# PowerSupply.net
KiCad netlist of a schematic drawn in EAGLE
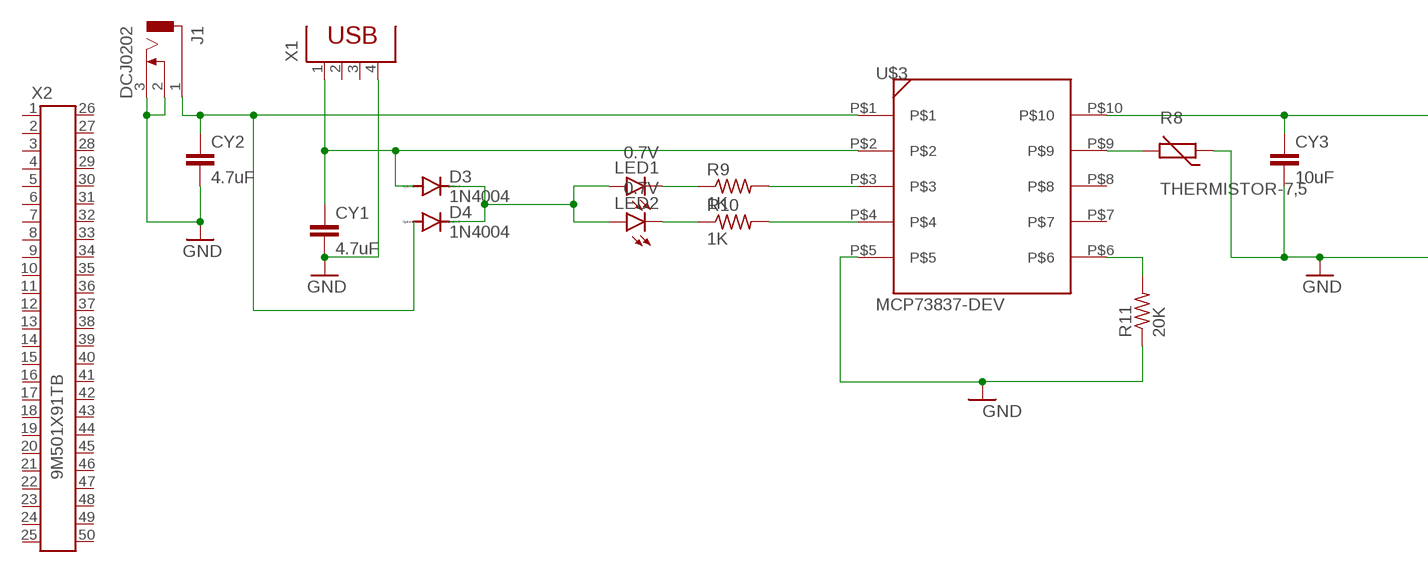
[diagram p0: schematic, sheet 1, part 1 of 2]
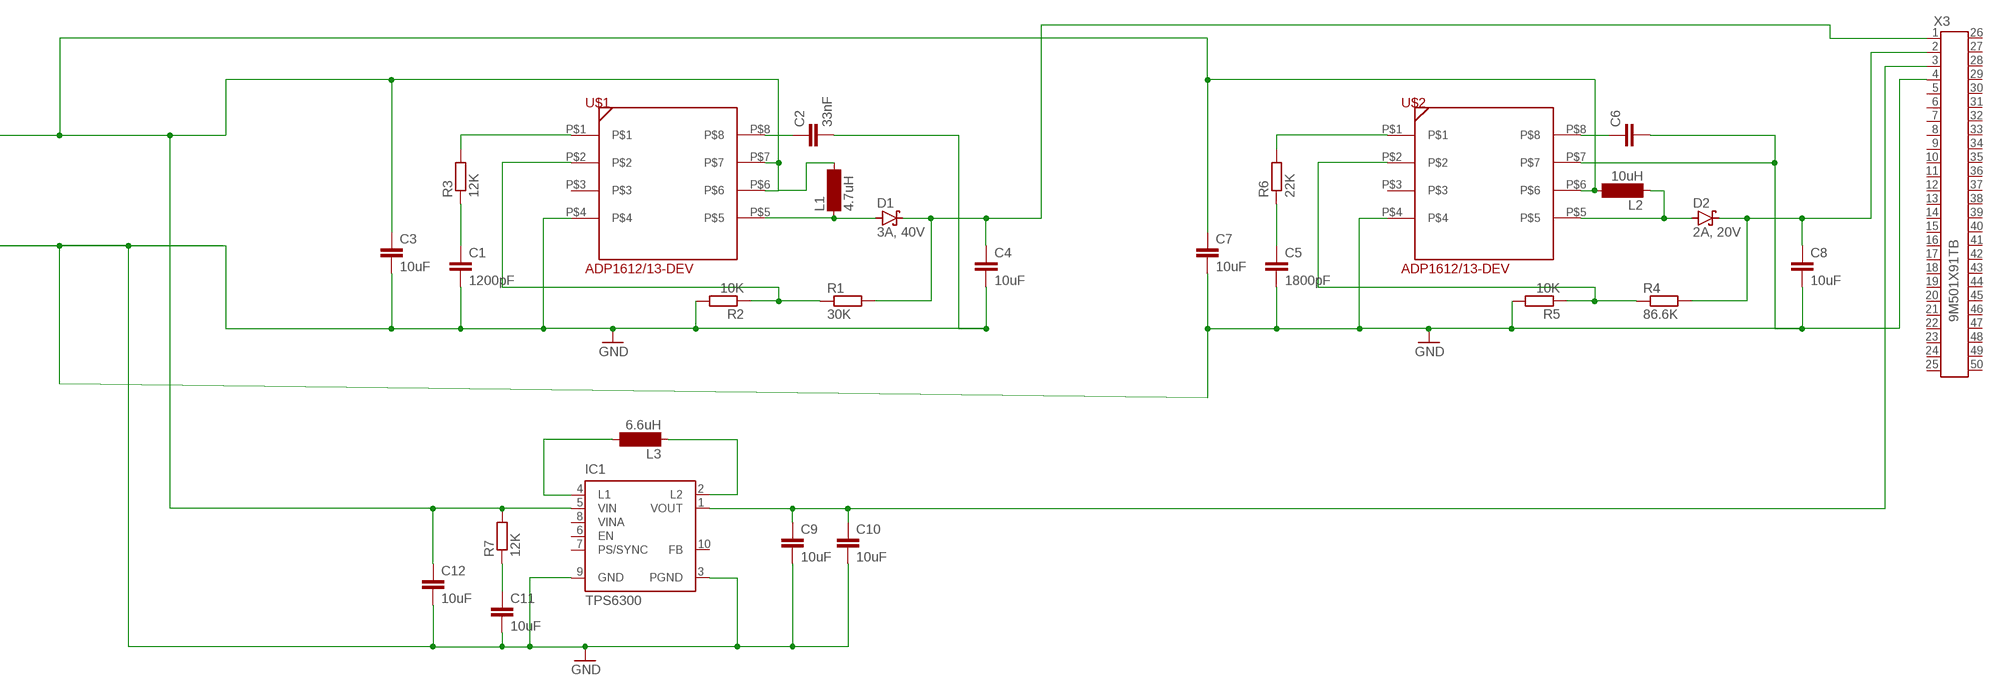
[diagram p1: schematic, sheet 1, part 2 of 2]

(export (version "E")
  (design (tool "Eeschema 10.0.6"))
  (components
    (comp (ref "C1")
      (value "1200pF")
      (footprint "eagle-import:C2.5-2")
      (libsource (lib "eagle-import") (part "C2.5/2"))
    )
    (comp (ref "C2")
      (value "33nF")
      (footprint "eagle-import:C2.5-2")
      (libsource (lib "eagle-import") (part "C2.5/2"))
    )
    (comp (ref "C3")
      (value "10uF")
      (footprint "eagle-import:C2.5-2")
      (libsource (lib "eagle-import") (part "C2.5/2"))
    )
    (comp (ref "C4")
      (value "10uF")
      (footprint "eagle-import:C2.5-2")
      (libsource (lib "eagle-import") (part "C2.5/2"))
    )
    (comp (ref "C5")
      (value "1800pF")
      (footprint "eagle-import:C2.5-2")
      (libsource (lib "eagle-import") (part "C2.5/2"))
    )
    (comp (ref "C6")
      (value "C2.5/2")
      (footprint "eagle-import:C2.5-2")
      (libsource (lib "eagle-import") (part "C2.5/2"))
    )
    (comp (ref "C7")
      (value "10uF")
      (footprint "eagle-import:C2.5-2")
      (libsource (lib "eagle-import") (part "C2.5/2"))
    )
    (comp (ref "C8")
      (value "10uF")
      (footprint "eagle-import:C2.5-2")
      (libsource (lib "eagle-import") (part "C2.5/2"))
    )
    (comp (ref "C9")
      (value "10uF")
      (footprint "eagle-import:C2.5-3")
      (libsource (lib "eagle-import") (part "C2,5-3"))
    )
    (comp (ref "C10")
      (value "10uF")
      (footprint "eagle-import:C2.5-3")
      (libsource (lib "eagle-import") (part "C2,5-3"))
    )
    (comp (ref "C11")
      (value "10uF")
      (footprint "eagle-import:C2.5-3")
      (libsource (lib "eagle-import") (part "C2,5-3"))
    )
    (comp (ref "C12")
      (value "10uF")
      (footprint "eagle-import:C2.5-3")
      (libsource (lib "eagle-import") (part "C2,5-3"))
    )
    (comp (ref "CY1")
      (value "4.7uF")
      (footprint "eagle-import:YC10B4")
      (libsource (lib "eagle-import") (part "CYYC10B4"))
    )
    (comp (ref "CY2")
      (value "4.7uF")
      (footprint "eagle-import:YC10B4")
      (libsource (lib "eagle-import") (part "CYYC10B4"))
    )
    (comp (ref "CY3")
      (value "10uF")
      (footprint "eagle-import:YC10B4")
      (libsource (lib "eagle-import") (part "CYYC10B4"))
    )
    (comp (ref "D1")
      (value "3A, 40V")
      (footprint "eagle-import:DO13M")
      (libsource (lib "eagle-import") (part "1N5638"))
    )
    (comp (ref "D2")
      (value "2A, 20V")
      (footprint "eagle-import:DO13M")
      (libsource (lib "eagle-import") (part "1N5638"))
    )
    (comp (ref "D3")
      (value "1N4004")
      (footprint "eagle-import:DO41-10")
      (libsource (lib "eagle-import") (part "1N4004"))
    )
    (comp (ref "D4")
      (value "1N4004")
      (footprint "eagle-import:DO41-10")
      (libsource (lib "eagle-import") (part "1N4004"))
    )
    (comp (ref "IC1")
      (value "TPS6300")
      (footprint "eagle-import:DRC-S-PVSON-N10")
      (fields (field (name "MPN") "TPS63000DRCTG4"))
      (libsource (lib "eagle-import") (part "TPS6300"))
    )
    (comp (ref "J1")
      (value "DCJ0202")
      (footprint "eagle-import:DCJ0202")
      (libsource (lib "eagle-import") (part "DCJ0202"))
    )
    (comp (ref "L1")
      (value "4.7uH")
      (footprint "eagle-import:SM-NE45")
      (libsource (lib "eagle-import") (part "SM-NE45"))
    )
    (comp (ref "L2")
      (value "10uH")
      (footprint "eagle-import:SM-NE45")
      (libsource (lib "eagle-import") (part "SM-NE45"))
    )
    (comp (ref "L3")
      (value "6.6uH")
      (footprint "eagle-import:SM-NE45")
      (libsource (lib "eagle-import") (part "SM-NE45"))
    )
    (comp (ref "LED1")
      (value "0.7V")
      (footprint "eagle-import:SMARTLED-TTW")
      (libsource (lib "eagle-import") (part "LED"))
    )
    (comp (ref "LED2")
      (value "0.7V")
      (footprint "eagle-import:SMARTLED-TTW")
      (libsource (lib "eagle-import") (part "LED"))
    )
    (comp (ref "R1")
      (value "30K")
      (footprint "eagle-import:0204V")
      (libsource (lib "eagle-import") (part "R-EU_0204/2V"))
    )
    (comp (ref "R2")
      (value "10K")
      (footprint "eagle-import:0204V")
      (libsource (lib "eagle-import") (part "R-EU_0204/2V"))
    )
    (comp (ref "R3")
      (value "12K")
      (footprint "eagle-import:0204V")
      (libsource (lib "eagle-import") (part "R-EU_0204/2V"))
    )
    (comp (ref "R4")
      (value "86.6K")
      (footprint "eagle-import:0204V")
      (libsource (lib "eagle-import") (part "R-EU_0204/2V"))
    )
    (comp (ref "R5")
      (value "10K")
      (footprint "eagle-import:0204V")
      (libsource (lib "eagle-import") (part "R-EU_0204/2V"))
    )
    (comp (ref "R6")
      (value "22K")
      (footprint "eagle-import:0204V")
      (libsource (lib "eagle-import") (part "R-EU_0204/2V"))
    )
    (comp (ref "R7")
      (value "12K")
      (footprint "eagle-import:0204V")
      (libsource (lib "eagle-import") (part "R-EU_0204/2V"))
    )
    (comp (ref "R8")
      (value "THERMISTOR-7,5")
      (footprint "eagle-import:R-7,5")
      (libsource (lib "eagle-import") (part "THERMISTOR-7,5"))
    )
    (comp (ref "R9")
      (value "1K")
      (footprint "eagle-import:0204V")
      (libsource (lib "eagle-import") (part "R-US_0204/2V"))
    )
    (comp (ref "R10")
      (value "1K")
      (footprint "eagle-import:0204V")
      (libsource (lib "eagle-import") (part "R-US_0204/2V"))
    )
    (comp (ref "R11")
      (value "20K")
      (footprint "eagle-import:0204V")
      (libsource (lib "eagle-import") (part "R-US_0204/2V"))
    )
    (comp (ref "U$1")
      (value "ADP1612/13-DEV")
      (footprint "eagle-import:ADP1612_13")
      (libsource (lib "eagle-import") (part "ADP1612/13-DEV"))
    )
    (comp (ref "U$2")
      (value "ADP1612/13-DEV")
      (footprint "eagle-import:ADP1612_13")
      (libsource (lib "eagle-import") (part "ADP1612/13-DEV"))
    )
    (comp (ref "U$3")
      (value "MCP73837-DEV")
      (footprint "eagle-import:MCP73837-FCI")
      (libsource (lib "eagle-import") (part "MCP73837-DEV"))
    )
    (comp (ref "X1")
      (value "PN61729")
      (footprint "eagle-import:PN61729")
      (libsource (lib "eagle-import") (part "PN61729"))
    )
    (comp (ref "X2")
      (value "9M501X91TB")
      (footprint "eagle-import:9M501X91")
      (libsource (lib "eagle-import") (part "9M501X91TB"))
    )
    (comp (ref "X3")
      (value "9M501X91TB")
      (footprint "eagle-import:9M501X91")
      (libsource (lib "eagle-import") (part "9M501X91TB"))
    )
  )
  (nets
    (net (code "1") (name "GND") (class "Default")
      (node (ref "C1") (pin "2") (pinfunction "2_2") (pintype "passive"))
      (node (ref "C10") (pin "2") (pinfunction "2_2") (pintype "passive"))
      (node (ref "C11") (pin "2") (pinfunction "2_2") (pintype "passive"))
      (node (ref "C12") (pin "2") (pinfunction "2_2") (pintype "passive"))
      (node (ref "C2") (pin "2") (pinfunction "2_2") (pintype "passive"))
      (node (ref "C3") (pin "2") (pinfunction "2_2") (pintype "passive"))
      (node (ref "C4") (pin "2") (pinfunction "2_2") (pintype "passive"))
      (node (ref "C5") (pin "2") (pinfunction "2_2") (pintype "passive"))
      (node (ref "C6") (pin "2") (pinfunction "2_2") (pintype "passive"))
      (node (ref "C7") (pin "2") (pinfunction "2_2") (pintype "passive"))
      (node (ref "C8") (pin "2") (pinfunction "2_2") (pintype "passive"))
      (node (ref "C9") (pin "2") (pinfunction "2_2") (pintype "passive"))
      (node (ref "CY1") (pin "2") (pinfunction "2_2") (pintype "passive"))
      (node (ref "CY2") (pin "2") (pinfunction "2_2") (pintype "passive"))
      (node (ref "CY3") (pin "2") (pinfunction "2_2") (pintype "passive"))
      (node (ref "IC1") (pin "3") (pinfunction "PGND_3") (pintype "power_in"))
      (node (ref "IC1") (pin "9") (pinfunction "GND_9") (pintype "power_in"))
      (node (ref "J1") (pin "2") (pinfunction "2_2") (pintype "passive"))
      (node (ref "J1") (pin "3") (pinfunction "3_3") (pintype "passive"))
      (node (ref "R11") (pin "1") (pinfunction "1_1") (pintype "passive"))
      (node (ref "R2") (pin "2") (pinfunction "2_2") (pintype "passive"))
      (node (ref "R5") (pin "2") (pinfunction "2_2") (pintype "passive"))
      (node (ref "R8") (pin "1") (pinfunction "1_1") (pintype "passive"))
      (node (ref "U$1") (pin "P$4") (pinfunction "P$4_P$4") (pintype "bidirectional"))
      (node (ref "U$2") (pin "P$4") (pinfunction "P$4_P$4") (pintype "bidirectional"))
      (node (ref "U$2") (pin "P$7") (pinfunction "P$7_P$7") (pintype "bidirectional"))
      (node (ref "U$3") (pin "P$5") (pinfunction "P$5_P$5") (pintype "bidirectional"))
      (node (ref "X1") (pin "4") (pinfunction "4_4") (pintype "passive"))
      (node (ref "X3") (pin "4") (pinfunction "4_4") (pintype "passive"))
    )
    (net (code "2") (name "Net-(C1-Pad1)") (class "Default")
      (node (ref "C1") (pin "1") (pinfunction "1_1") (pintype "passive"))
      (node (ref "R3") (pin "1") (pinfunction "1_1") (pintype "passive"))
    )
    (net (code "3") (name "Net-(C2-Pad1)") (class "Default")
      (node (ref "C2") (pin "1") (pinfunction "1_1") (pintype "passive"))
      (node (ref "U$1") (pin "P$8") (pinfunction "P$8_P$8") (pintype "bidirectional"))
    )
    (net (code "4") (name "Net-(C4-Pad1)") (class "Default")
      (node (ref "C4") (pin "1") (pinfunction "1_1") (pintype "passive"))
      (node (ref "D1") (pin "C") (pinfunction "C_C") (pintype "passive"))
      (node (ref "R1") (pin "2") (pinfunction "2_2") (pintype "passive"))
      (node (ref "X3") (pin "1") (pinfunction "1_1") (pintype "passive"))
    )
    (net (code "5") (name "Net-(C5-Pad1)") (class "Default")
      (node (ref "C5") (pin "1") (pinfunction "1_1") (pintype "passive"))
      (node (ref "R6") (pin "1") (pinfunction "1_1") (pintype "passive"))
    )
    (net (code "6") (name "Net-(C6-Pad1)") (class "Default")
      (node (ref "C6") (pin "1") (pinfunction "1_1") (pintype "passive"))
      (node (ref "U$2") (pin "P$8") (pinfunction "P$8_P$8") (pintype "bidirectional"))
    )
    (net (code "7") (name "Net-(C8-Pad1)") (class "Default")
      (node (ref "C8") (pin "1") (pinfunction "1_1") (pintype "passive"))
      (node (ref "D2") (pin "C") (pinfunction "C_C") (pintype "passive"))
      (node (ref "R4") (pin "2") (pinfunction "2_2") (pintype "passive"))
      (node (ref "X3") (pin "2") (pinfunction "2_2") (pintype "passive"))
    )
    (net (code "8") (name "Net-(C11-Pad1)") (class "Default")
      (node (ref "C11") (pin "1") (pinfunction "1_1") (pintype "passive"))
      (node (ref "R7") (pin "1") (pinfunction "1_1") (pintype "passive"))
    )
    (net (code "9") (name "Net-(CY1-Pad1)") (class "Default")
      (node (ref "CY1") (pin "1") (pinfunction "1_1") (pintype "passive"))
      (node (ref "D3") (pin "A") (pinfunction "A_A") (pintype "passive"))
      (node (ref "U$3") (pin "P$2") (pinfunction "P$2_P$2") (pintype "bidirectional"))
      (node (ref "X1") (pin "1") (pinfunction "1_1") (pintype "passive"))
    )
    (net (code "10") (name "Net-(CY2-Pad1)") (class "Default")
      (node (ref "CY2") (pin "1") (pinfunction "1_1") (pintype "passive"))
      (node (ref "D4") (pin "A") (pinfunction "A_A") (pintype "passive"))
      (node (ref "J1") (pin "1") (pinfunction "1_1") (pintype "passive"))
      (node (ref "U$3") (pin "P$1") (pinfunction "P$1_P$1") (pintype "bidirectional"))
    )
    (net (code "11") (name "Net-(D1-PadA)") (class "Default")
      (node (ref "D1") (pin "A") (pinfunction "A_A") (pintype "passive"))
      (node (ref "L1") (pin "1") (pinfunction "1_1") (pintype "passive"))
      (node (ref "U$1") (pin "P$5") (pinfunction "P$5_P$5") (pintype "bidirectional"))
    )
    (net (code "12") (name "Net-(D2-PadA)") (class "Default")
      (node (ref "D2") (pin "A") (pinfunction "A_A") (pintype "passive"))
      (node (ref "L2") (pin "1") (pinfunction "1_1") (pintype "passive"))
      (node (ref "U$2") (pin "P$5") (pinfunction "P$5_P$5") (pintype "bidirectional"))
    )
    (net (code "13") (name "Net-(IC1A-L1)") (class "Default")
      (node (ref "IC1") (pin "4") (pinfunction "L1_4") (pintype "passive"))
      (node (ref "L3") (pin "2") (pinfunction "2_2") (pintype "passive"))
    )
    (net (code "14") (name "Net-(IC1A-L2)") (class "Default")
      (node (ref "IC1") (pin "2") (pinfunction "L2_2") (pintype "passive"))
      (node (ref "L3") (pin "1") (pinfunction "1_1") (pintype "passive"))
    )
    (net (code "15") (name "Net-(IC1A-VIN)") (class "Default")
      (node (ref "C12") (pin "1") (pinfunction "1_1") (pintype "passive"))
      (node (ref "C3") (pin "1") (pinfunction "1_1") (pintype "passive"))
      (node (ref "C7") (pin "1") (pinfunction "1_1") (pintype "passive"))
      (node (ref "CY3") (pin "1") (pinfunction "1_1") (pintype "passive"))
      (node (ref "IC1") (pin "5") (pinfunction "VIN_5") (pintype "input"))
      (node (ref "L1") (pin "2") (pinfunction "2_2") (pintype "passive"))
      (node (ref "L2") (pin "2") (pinfunction "2_2") (pintype "passive"))
      (node (ref "R7") (pin "2") (pinfunction "2_2") (pintype "passive"))
      (node (ref "U$1") (pin "P$6") (pinfunction "P$6_P$6") (pintype "bidirectional"))
      (node (ref "U$1") (pin "P$7") (pinfunction "P$7_P$7") (pintype "bidirectional"))
      (node (ref "U$2") (pin "P$6") (pinfunction "P$6_P$6") (pintype "bidirectional"))
      (node (ref "U$3") (pin "P$10") (pinfunction "P$10_P$10") (pintype "bidirectional"))
    )
    (net (code "16") (name "Net-(IC1A-VOUT)") (class "Default")
      (node (ref "C10") (pin "1") (pinfunction "1_1") (pintype "passive"))
      (node (ref "C9") (pin "1") (pinfunction "1_1") (pintype "passive"))
      (node (ref "IC1") (pin "1") (pinfunction "VOUT_1") (pintype "output"))
      (node (ref "X3") (pin "3") (pinfunction "3_3") (pintype "passive"))
    )
    (net (code "17") (name "Net-(LED1-A)") (class "Default")
      (node (ref "D3") (pin "C") (pinfunction "C_C") (pintype "passive"))
      (node (ref "D4") (pin "C") (pinfunction "C_C") (pintype "passive"))
      (node (ref "LED1") (pin "A@1") (pinfunction "A_A@1") (pintype "passive"))
      (node (ref "LED2") (pin "A@1") (pinfunction "A_A@1") (pintype "passive"))
    )
    (net (code "18") (name "Net-(LED1-C)") (class "Default")
      (node (ref "LED1") (pin "C@1") (pinfunction "C_C@1") (pintype "passive"))
      (node (ref "R9") (pin "1") (pinfunction "1_1") (pintype "passive"))
    )
    (net (code "19") (name "Net-(LED2-C)") (class "Default")
      (node (ref "LED2") (pin "C@1") (pinfunction "C_C@1") (pintype "passive"))
      (node (ref "R10") (pin "1") (pinfunction "1_1") (pintype "passive"))
    )
    (net (code "20") (name "Net-(R1-Pad1)") (class "Default")
      (node (ref "R1") (pin "1") (pinfunction "1_1") (pintype "passive"))
      (node (ref "R2") (pin "1") (pinfunction "1_1") (pintype "passive"))
      (node (ref "U$1") (pin "P$2") (pinfunction "P$2_P$2") (pintype "bidirectional"))
    )
    (net (code "21") (name "Net-(R3-Pad2)") (class "Default")
      (node (ref "R3") (pin "2") (pinfunction "2_2") (pintype "passive"))
      (node (ref "U$1") (pin "P$1") (pinfunction "P$1_P$1") (pintype "bidirectional"))
    )
    (net (code "22") (name "Net-(R4-Pad1)") (class "Default")
      (node (ref "R4") (pin "1") (pinfunction "1_1") (pintype "passive"))
      (node (ref "R5") (pin "1") (pinfunction "1_1") (pintype "passive"))
      (node (ref "U$2") (pin "P$2") (pinfunction "P$2_P$2") (pintype "bidirectional"))
    )
    (net (code "23") (name "Net-(R6-Pad2)") (class "Default")
      (node (ref "R6") (pin "2") (pinfunction "2_2") (pintype "passive"))
      (node (ref "U$2") (pin "P$1") (pinfunction "P$1_P$1") (pintype "bidirectional"))
    )
    (net (code "24") (name "Net-(R8-Pad2)") (class "Default")
      (node (ref "R8") (pin "2") (pinfunction "2_2") (pintype "passive"))
      (node (ref "U$3") (pin "P$9") (pinfunction "P$9_P$9") (pintype "bidirectional"))
    )
    (net (code "25") (name "Net-(R9-Pad2)") (class "Default")
      (node (ref "R9") (pin "2") (pinfunction "2_2") (pintype "passive"))
      (node (ref "U$3") (pin "P$3") (pinfunction "P$3_P$3") (pintype "bidirectional"))
    )
    (net (code "26") (name "Net-(R10-Pad2)") (class "Default")
      (node (ref "R10") (pin "2") (pinfunction "2_2") (pintype "passive"))
      (node (ref "U$3") (pin "P$4") (pinfunction "P$4_P$4") (pintype "bidirectional"))
    )
    (net (code "27") (name "Net-(R11-Pad2)") (class "Default")
      (node (ref "R11") (pin "2") (pinfunction "2_2") (pintype "passive"))
      (node (ref "U$3") (pin "P$6") (pinfunction "P$6_P$6") (pintype "bidirectional"))
    )
    (net (code "28") (name "unconnected-(IC1A-EN-Pad6)") (class "Default")
      (node (ref "IC1") (pin "6") (pinfunction "EN_6") (pintype "input"))
    )
    (net (code "29") (name "unconnected-(IC1A-FB-Pad10)") (class "Default")
      (node (ref "IC1") (pin "10") (pinfunction "FB_10") (pintype "input"))
    )
    (net (code "30") (name "unconnected-(IC1A-PS{slash}SYNC-Pad7)") (class "Default")
      (node (ref "IC1") (pin "7") (pinfunction "PS/SYNC_7") (pintype "input"))
    )
    (net (code "31") (name "unconnected-(IC1A-VINA-Pad8)") (class "Default")
      (node (ref "IC1") (pin "8") (pinfunction "VINA_8") (pintype "input"))
    )
    (net (code "32") (name "unconnected-(U$1-PadP$3)") (class "Default")
      (node (ref "U$1") (pin "P$3") (pinfunction "P$3_P$3") (pintype "bidirectional"))
    )
    (net (code "33") (name "unconnected-(U$2-PadP$3)") (class "Default")
      (node (ref "U$2") (pin "P$3") (pinfunction "P$3_P$3") (pintype "bidirectional"))
    )
    (net (code "34") (name "unconnected-(U$3-PadP$7)") (class "Default")
      (node (ref "U$3") (pin "P$7") (pinfunction "P$7_P$7") (pintype "bidirectional"))
    )
    (net (code "35") (name "unconnected-(U$3-PadP$8)") (class "Default")
      (node (ref "U$3") (pin "P$8") (pinfunction "P$8_P$8") (pintype "bidirectional"))
    )
    (net (code "36") (name "unconnected-(X1-Pad2)") (class "Default")
      (node (ref "X1") (pin "2") (pinfunction "2_2") (pintype "passive"))
    )
    (net (code "37") (name "unconnected-(X1-Pad3)") (class "Default")
      (node (ref "X1") (pin "3") (pinfunction "3_3") (pintype "passive"))
    )
    (net (code "38") (name "unconnected-(X2-Pad1)") (class "Default")
      (node (ref "X2") (pin "1") (pinfunction "1_1") (pintype "passive"))
    )
    (net (code "39") (name "unconnected-(X2-Pad2)") (class "Default")
      (node (ref "X2") (pin "2") (pinfunction "2_2") (pintype "passive"))
    )
    (net (code "40") (name "unconnected-(X2-Pad3)") (class "Default")
      (node (ref "X2") (pin "3") (pinfunction "3_3") (pintype "passive"))
    )
    (net (code "41") (name "unconnected-(X2-Pad4)") (class "Default")
      (node (ref "X2") (pin "4") (pinfunction "4_4") (pintype "passive"))
    )
    (net (code "42") (name "unconnected-(X2-Pad5)") (class "Default")
      (node (ref "X2") (pin "5") (pinfunction "5_5") (pintype "passive"))
    )
    (net (code "43") (name "unconnected-(X2-Pad6)") (class "Default")
      (node (ref "X2") (pin "6") (pinfunction "6_6") (pintype "passive"))
    )
    (net (code "44") (name "unconnected-(X2-Pad7)") (class "Default")
      (node (ref "X2") (pin "7") (pinfunction "7_7") (pintype "passive"))
    )
    (net (code "45") (name "unconnected-(X2-Pad8)") (class "Default")
      (node (ref "X2") (pin "8") (pinfunction "8_8") (pintype "passive"))
    )
    (net (code "46") (name "unconnected-(X2-Pad9)") (class "Default")
      (node (ref "X2") (pin "9") (pinfunction "9_9") (pintype "passive"))
    )
    (net (code "47") (name "unconnected-(X2-Pad10)") (class "Default")
      (node (ref "X2") (pin "10") (pinfunction "10_10") (pintype "passive"))
    )
    (net (code "48") (name "unconnected-(X2-Pad11)") (class "Default")
      (node (ref "X2") (pin "11") (pinfunction "11_11") (pintype "passive"))
    )
    (net (code "49") (name "unconnected-(X2-Pad12)") (class "Default")
      (node (ref "X2") (pin "12") (pinfunction "12_12") (pintype "passive"))
    )
    (net (code "50") (name "unconnected-(X2-Pad13)") (class "Default")
      (node (ref "X2") (pin "13") (pinfunction "13_13") (pintype "passive"))
    )
    (net (code "51") (name "unconnected-(X2-Pad14)") (class "Default")
      (node (ref "X2") (pin "14") (pinfunction "14_14") (pintype "passive"))
    )
    (net (code "52") (name "unconnected-(X2-Pad15)") (class "Default")
      (node (ref "X2") (pin "15") (pinfunction "15_15") (pintype "passive"))
    )
    (net (code "53") (name "unconnected-(X2-Pad16)") (class "Default")
      (node (ref "X2") (pin "16") (pinfunction "16_16") (pintype "passive"))
    )
    (net (code "54") (name "unconnected-(X2-Pad17)") (class "Default")
      (node (ref "X2") (pin "17") (pinfunction "17_17") (pintype "passive"))
    )
    (net (code "55") (name "unconnected-(X2-Pad18)") (class "Default")
      (node (ref "X2") (pin "18") (pinfunction "18_18") (pintype "passive"))
    )
    (net (code "56") (name "unconnected-(X2-Pad19)") (class "Default")
      (node (ref "X2") (pin "19") (pinfunction "19_19") (pintype "passive"))
    )
    (net (code "57") (name "unconnected-(X2-Pad20)") (class "Default")
      (node (ref "X2") (pin "20") (pinfunction "20_20") (pintype "passive"))
    )
    (net (code "58") (name "unconnected-(X2-Pad21)") (class "Default")
      (node (ref "X2") (pin "21") (pinfunction "21_21") (pintype "passive"))
    )
    (net (code "59") (name "unconnected-(X2-Pad22)") (class "Default")
      (node (ref "X2") (pin "22") (pinfunction "22_22") (pintype "passive"))
    )
    (net (code "60") (name "unconnected-(X2-Pad23)") (class "Default")
      (node (ref "X2") (pin "23") (pinfunction "23_23") (pintype "passive"))
    )
    (net (code "61") (name "unconnected-(X2-Pad24)") (class "Default")
      (node (ref "X2") (pin "24") (pinfunction "24_24") (pintype "passive"))
    )
    (net (code "62") (name "unconnected-(X2-Pad25)") (class "Default")
      (node (ref "X2") (pin "25") (pinfunction "25_25") (pintype "passive"))
    )
    (net (code "63") (name "unconnected-(X2-Pad26)") (class "Default")
      (node (ref "X2") (pin "26") (pinfunction "26_26") (pintype "passive"))
    )
    (net (code "64") (name "unconnected-(X2-Pad27)") (class "Default")
      (node (ref "X2") (pin "27") (pinfunction "27_27") (pintype "passive"))
    )
    (net (code "65") (name "unconnected-(X2-Pad28)") (class "Default")
      (node (ref "X2") (pin "28") (pinfunction "28_28") (pintype "passive"))
    )
    (net (code "66") (name "unconnected-(X2-Pad29)") (class "Default")
      (node (ref "X2") (pin "29") (pinfunction "29_29") (pintype "passive"))
    )
    (net (code "67") (name "unconnected-(X2-Pad30)") (class "Default")
      (node (ref "X2") (pin "30") (pinfunction "30_30") (pintype "passive"))
    )
    (net (code "68") (name "unconnected-(X2-Pad31)") (class "Default")
      (node (ref "X2") (pin "31") (pinfunction "31_31") (pintype "passive"))
    )
    (net (code "69") (name "unconnected-(X2-Pad32)") (class "Default")
      (node (ref "X2") (pin "32") (pinfunction "32_32") (pintype "passive"))
    )
    (net (code "70") (name "unconnected-(X2-Pad33)") (class "Default")
      (node (ref "X2") (pin "33") (pinfunction "33_33") (pintype "passive"))
    )
    (net (code "71") (name "unconnected-(X2-Pad34)") (class "Default")
      (node (ref "X2") (pin "34") (pinfunction "34_34") (pintype "passive"))
    )
    (net (code "72") (name "unconnected-(X2-Pad35)") (class "Default")
      (node (ref "X2") (pin "35") (pinfunction "35_35") (pintype "passive"))
    )
    (net (code "73") (name "unconnected-(X2-Pad36)") (class "Default")
      (node (ref "X2") (pin "36") (pinfunction "36_36") (pintype "passive"))
    )
    (net (code "74") (name "unconnected-(X2-Pad37)") (class "Default")
      (node (ref "X2") (pin "37") (pinfunction "37_37") (pintype "passive"))
    )
    (net (code "75") (name "unconnected-(X2-Pad38)") (class "Default")
      (node (ref "X2") (pin "38") (pinfunction "38_38") (pintype "passive"))
    )
    (net (code "76") (name "unconnected-(X2-Pad39)") (class "Default")
      (node (ref "X2") (pin "39") (pinfunction "39_39") (pintype "passive"))
    )
    (net (code "77") (name "unconnected-(X2-Pad40)") (class "Default")
      (node (ref "X2") (pin "40") (pinfunction "40_40") (pintype "passive"))
    )
    (net (code "78") (name "unconnected-(X2-Pad41)") (class "Default")
      (node (ref "X2") (pin "41") (pinfunction "41_41") (pintype "passive"))
    )
    (net (code "79") (name "unconnected-(X2-Pad42)") (class "Default")
      (node (ref "X2") (pin "42") (pinfunction "42_42") (pintype "passive"))
    )
    (net (code "80") (name "unconnected-(X2-Pad43)") (class "Default")
      (node (ref "X2") (pin "43") (pinfunction "43_43") (pintype "passive"))
    )
    (net (code "81") (name "unconnected-(X2-Pad44)") (class "Default")
      (node (ref "X2") (pin "44") (pinfunction "44_44") (pintype "passive"))
    )
    (net (code "82") (name "unconnected-(X2-Pad45)") (class "Default")
      (node (ref "X2") (pin "45") (pinfunction "45_45") (pintype "passive"))
    )
    (net (code "83") (name "unconnected-(X2-Pad46)") (class "Default")
      (node (ref "X2") (pin "46") (pinfunction "46_46") (pintype "passive"))
    )
    (net (code "84") (name "unconnected-(X2-Pad47)") (class "Default")
      (node (ref "X2") (pin "47") (pinfunction "47_47") (pintype "passive"))
    )
    (net (code "85") (name "unconnected-(X2-Pad48)") (class "Default")
      (node (ref "X2") (pin "48") (pinfunction "48_48") (pintype "passive"))
    )
    (net (code "86") (name "unconnected-(X2-Pad49)") (class "Default")
      (node (ref "X2") (pin "49") (pinfunction "49_49") (pintype "passive"))
    )
    (net (code "87") (name "unconnected-(X2-Pad50)") (class "Default")
      (node (ref "X2") (pin "50") (pinfunction "50_50") (pintype "passive"))
    )
    (net (code "88") (name "unconnected-(X3-Pad5)") (class "Default")
      (node (ref "X3") (pin "5") (pinfunction "5_5") (pintype "passive"))
    )
    (net (code "89") (name "unconnected-(X3-Pad6)") (class "Default")
      (node (ref "X3") (pin "6") (pinfunction "6_6") (pintype "passive"))
    )
    (net (code "90") (name "unconnected-(X3-Pad7)") (class "Default")
      (node (ref "X3") (pin "7") (pinfunction "7_7") (pintype "passive"))
    )
    (net (code "91") (name "unconnected-(X3-Pad8)") (class "Default")
      (node (ref "X3") (pin "8") (pinfunction "8_8") (pintype "passive"))
    )
    (net (code "92") (name "unconnected-(X3-Pad9)") (class "Default")
      (node (ref "X3") (pin "9") (pinfunction "9_9") (pintype "passive"))
    )
    (net (code "93") (name "unconnected-(X3-Pad10)") (class "Default")
      (node (ref "X3") (pin "10") (pinfunction "10_10") (pintype "passive"))
    )
    (net (code "94") (name "unconnected-(X3-Pad11)") (class "Default")
      (node (ref "X3") (pin "11") (pinfunction "11_11") (pintype "passive"))
    )
    (net (code "95") (name "unconnected-(X3-Pad12)") (class "Default")
      (node (ref "X3") (pin "12") (pinfunction "12_12") (pintype "passive"))
    )
    (net (code "96") (name "unconnected-(X3-Pad13)") (class "Default")
      (node (ref "X3") (pin "13") (pinfunction "13_13") (pintype "passive"))
    )
    (net (code "97") (name "unconnected-(X3-Pad14)") (class "Default")
      (node (ref "X3") (pin "14") (pinfunction "14_14") (pintype "passive"))
    )
    (net (code "98") (name "unconnected-(X3-Pad15)") (class "Default")
      (node (ref "X3") (pin "15") (pinfunction "15_15") (pintype "passive"))
    )
    (net (code "99") (name "unconnected-(X3-Pad16)") (class "Default")
      (node (ref "X3") (pin "16") (pinfunction "16_16") (pintype "passive"))
    )
    (net (code "100") (name "unconnected-(X3-Pad17)") (class "Default")
      (node (ref "X3") (pin "17") (pinfunction "17_17") (pintype "passive"))
    )
    (net (code "101") (name "unconnected-(X3-Pad18)") (class "Default")
      (node (ref "X3") (pin "18") (pinfunction "18_18") (pintype "passive"))
    )
    (net (code "102") (name "unconnected-(X3-Pad19)") (class "Default")
      (node (ref "X3") (pin "19") (pinfunction "19_19") (pintype "passive"))
    )
    (net (code "103") (name "unconnected-(X3-Pad20)") (class "Default")
      (node (ref "X3") (pin "20") (pinfunction "20_20") (pintype "passive"))
    )
    (net (code "104") (name "unconnected-(X3-Pad21)") (class "Default")
      (node (ref "X3") (pin "21") (pinfunction "21_21") (pintype "passive"))
    )
    (net (code "105") (name "unconnected-(X3-Pad22)") (class "Default")
      (node (ref "X3") (pin "22") (pinfunction "22_22") (pintype "passive"))
    )
    (net (code "106") (name "unconnected-(X3-Pad23)") (class "Default")
      (node (ref "X3") (pin "23") (pinfunction "23_23") (pintype "passive"))
    )
    (net (code "107") (name "unconnected-(X3-Pad24)") (class "Default")
      (node (ref "X3") (pin "24") (pinfunction "24_24") (pintype "passive"))
    )
    (net (code "108") (name "unconnected-(X3-Pad25)") (class "Default")
      (node (ref "X3") (pin "25") (pinfunction "25_25") (pintype "passive"))
    )
    (net (code "109") (name "unconnected-(X3-Pad26)") (class "Default")
      (node (ref "X3") (pin "26") (pinfunction "26_26") (pintype "passive"))
    )
    (net (code "110") (name "unconnected-(X3-Pad27)") (class "Default")
      (node (ref "X3") (pin "27") (pinfunction "27_27") (pintype "passive"))
    )
    (net (code "111") (name "unconnected-(X3-Pad28)") (class "Default")
      (node (ref "X3") (pin "28") (pinfunction "28_28") (pintype "passive"))
    )
    (net (code "112") (name "unconnected-(X3-Pad29)") (class "Default")
      (node (ref "X3") (pin "29") (pinfunction "29_29") (pintype "passive"))
    )
    (net (code "113") (name "unconnected-(X3-Pad30)") (class "Default")
      (node (ref "X3") (pin "30") (pinfunction "30_30") (pintype "passive"))
    )
    (net (code "114") (name "unconnected-(X3-Pad31)") (class "Default")
      (node (ref "X3") (pin "31") (pinfunction "31_31") (pintype "passive"))
    )
    (net (code "115") (name "unconnected-(X3-Pad32)") (class "Default")
      (node (ref "X3") (pin "32") (pinfunction "32_32") (pintype "passive"))
    )
    (net (code "116") (name "unconnected-(X3-Pad33)") (class "Default")
      (node (ref "X3") (pin "33") (pinfunction "33_33") (pintype "passive"))
    )
    (net (code "117") (name "unconnected-(X3-Pad34)") (class "Default")
      (node (ref "X3") (pin "34") (pinfunction "34_34") (pintype "passive"))
    )
    (net (code "118") (name "unconnected-(X3-Pad35)") (class "Default")
      (node (ref "X3") (pin "35") (pinfunction "35_35") (pintype "passive"))
    )
    (net (code "119") (name "unconnected-(X3-Pad36)") (class "Default")
      (node (ref "X3") (pin "36") (pinfunction "36_36") (pintype "passive"))
    )
    (net (code "120") (name "unconnected-(X3-Pad37)") (class "Default")
      (node (ref "X3") (pin "37") (pinfunction "37_37") (pintype "passive"))
    )
    (net (code "121") (name "unconnected-(X3-Pad38)") (class "Default")
      (node (ref "X3") (pin "38") (pinfunction "38_38") (pintype "passive"))
    )
    (net (code "122") (name "unconnected-(X3-Pad39)") (class "Default")
      (node (ref "X3") (pin "39") (pinfunction "39_39") (pintype "passive"))
    )
    (net (code "123") (name "unconnected-(X3-Pad40)") (class "Default")
      (node (ref "X3") (pin "40") (pinfunction "40_40") (pintype "passive"))
    )
    (net (code "124") (name "unconnected-(X3-Pad41)") (class "Default")
      (node (ref "X3") (pin "41") (pinfunction "41_41") (pintype "passive"))
    )
    (net (code "125") (name "unconnected-(X3-Pad42)") (class "Default")
      (node (ref "X3") (pin "42") (pinfunction "42_42") (pintype "passive"))
    )
    (net (code "126") (name "unconnected-(X3-Pad43)") (class "Default")
      (node (ref "X3") (pin "43") (pinfunction "43_43") (pintype "passive"))
    )
    (net (code "127") (name "unconnected-(X3-Pad44)") (class "Default")
      (node (ref "X3") (pin "44") (pinfunction "44_44") (pintype "passive"))
    )
    (net (code "128") (name "unconnected-(X3-Pad45)") (class "Default")
      (node (ref "X3") (pin "45") (pinfunction "45_45") (pintype "passive"))
    )
    (net (code "129") (name "unconnected-(X3-Pad46)") (class "Default")
      (node (ref "X3") (pin "46") (pinfunction "46_46") (pintype "passive"))
    )
    (net (code "130") (name "unconnected-(X3-Pad47)") (class "Default")
      (node (ref "X3") (pin "47") (pinfunction "47_47") (pintype "passive"))
    )
    (net (code "131") (name "unconnected-(X3-Pad48)") (class "Default")
      (node (ref "X3") (pin "48") (pinfunction "48_48") (pintype "passive"))
    )
    (net (code "132") (name "unconnected-(X3-Pad49)") (class "Default")
      (node (ref "X3") (pin "49") (pinfunction "49_49") (pintype "passive"))
    )
    (net (code "133") (name "unconnected-(X3-Pad50)") (class "Default")
      (node (ref "X3") (pin "50") (pinfunction "50_50") (pintype "passive"))
    )
  )
)
